# S7CAS-PLEIADES-CARTE-MERE_Pxx_IO_SENSOR.net
KiCad netlist of a schematic drawn in Altium Designer
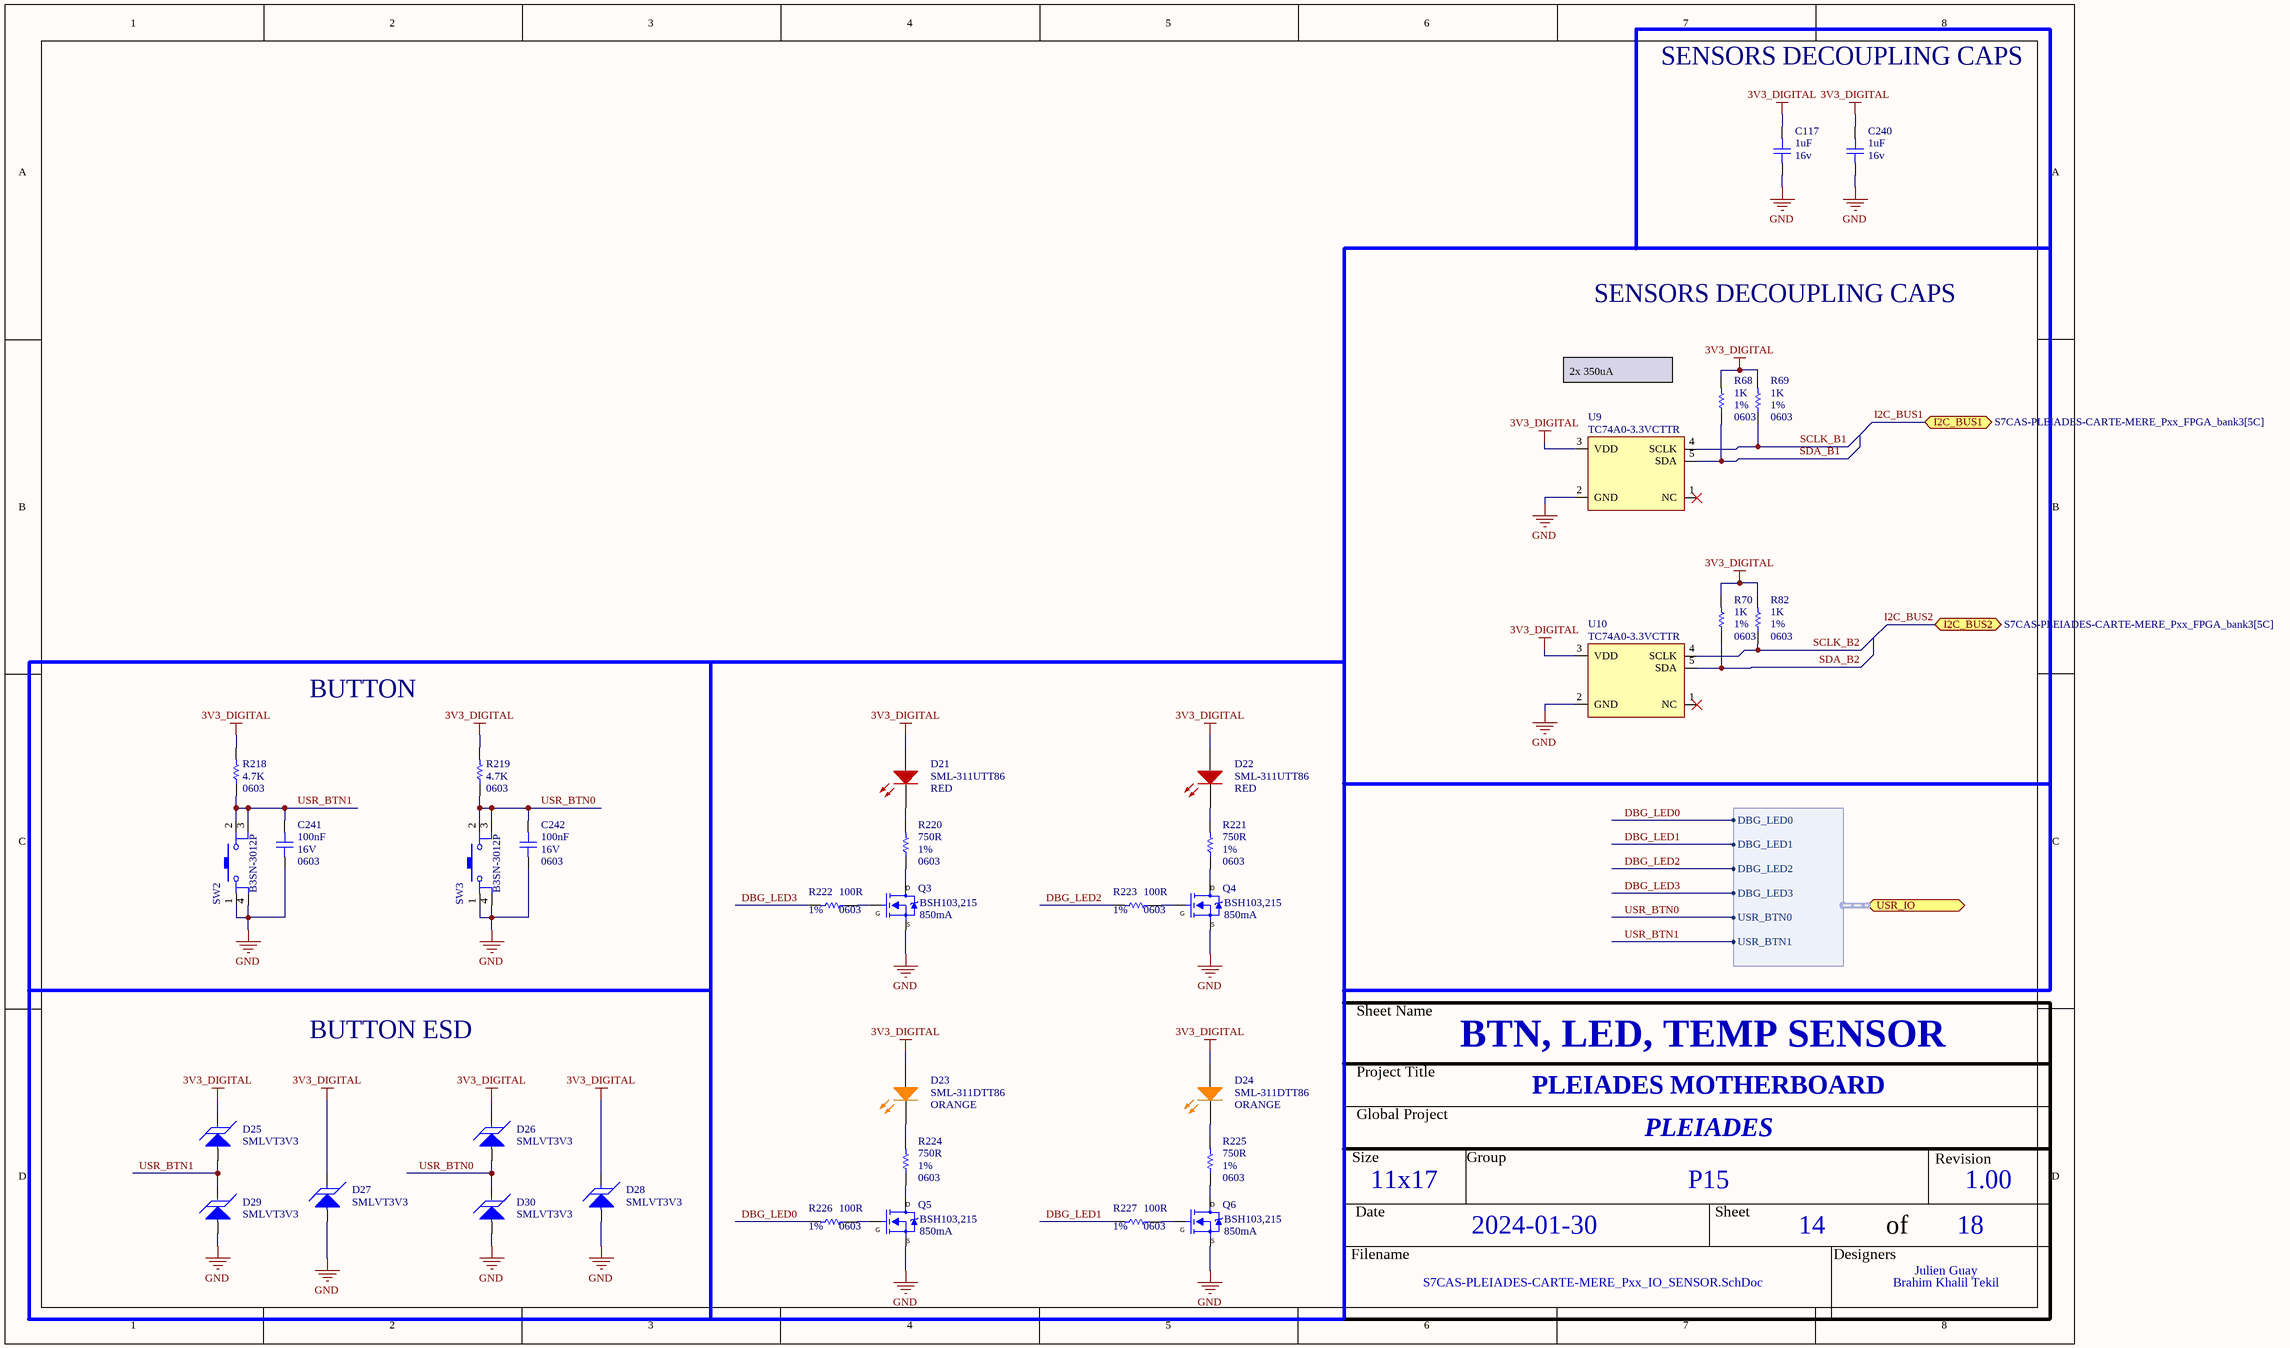
[diagram p0: S7CAS-PLEIADES-CARTE-MERE_Pxx_IO_SENSOR.SchDoc]

(export (version "E")
  (design (tool "Eeschema 10.0.6"))
  (components
    (comp (ref "C117")
      (value "1uF")
      (footprint "CAP_0603")
      (description "CAP - 0603")
      (fields (field (name "VOLTAGE") "16v") (field (name "CREATEDBY") "Jonathan Bouchard"))
      (libsource (lib "S7CAS_LIB2023") (part "CAP - 0603"))
    )
    (comp (ref "C240")
      (value "1uF")
      (footprint "CAP_0603")
      (description "CAP - 0603")
      (fields (field (name "VOLTAGE") "16v") (field (name "CREATEDBY") "Jonathan Bouchard"))
      (libsource (lib "S7CAS_LIB2023") (part "CAP - 0603"))
    )
    (comp (ref "C241")
      (value "100nF")
      (footprint "CAP_0603")
      (description "CAP - 0603")
      (fields
        (field (name "VOLTAGE") "16V")
        (field (name "PACKAGE") "0603")
        (field (name "CREATEDBY") "Jonathan Bouchard")
      )
      (libsource (lib "S7CAS_LIB2023") (part "CAP - 0603"))
    )
    (comp (ref "C242")
      (value "100nF")
      (footprint "CAP_0603")
      (description "CAP - 0603")
      (fields
        (field (name "VOLTAGE") "16V")
        (field (name "PACKAGE") "0603")
        (field (name "CREATEDBY") "Jonathan Bouchard")
      )
      (libsource (lib "S7CAS_LIB2023") (part "CAP - 0603"))
    )
    (comp (ref "D21")
      (value "SML-311UTT86")
      (footprint "LED_0603")
      (description "LED - 620nM RED 2mA - 0603")
      (fields
        (field (name "VOLTAGE") "1.8V")
        (field (name "MFG") "ROHM Semiconductor")
        (field (name "ALTIUM_VALUE") "RED")
        (field (name "CREATEDBY") "Jonathan Bouchard")
      )
      (libsource (lib "S7CAS_LIB2023") (part "LED_SML-311UTT86"))
    )
    (comp (ref "D22")
      (value "SML-311UTT86")
      (footprint "LED_0603")
      (description "LED - 620nM RED 2mA - 0603")
      (fields
        (field (name "VOLTAGE") "1.8V")
        (field (name "MFG") "ROHM Semiconductor")
        (field (name "ALTIUM_VALUE") "RED")
        (field (name "CREATEDBY") "Jonathan Bouchard")
      )
      (libsource (lib "S7CAS_LIB2023") (part "LED_SML-311UTT86"))
    )
    (comp (ref "D23")
      (value "SML-311DTT86")
      (footprint "LED_0603")
      (description "LED - 611nM ORANGE 2mA - 0603")
      (fields
        (field (name "VOLTAGE") "1.8V")
        (field (name "MFG") "ROHM Semiconductor")
        (field (name "ALTIUM_VALUE") "ORANGE")
        (field (name "CREATEDBY") "Jonathan Bouchard")
      )
      (libsource (lib "S7CAS_LIB2023") (part "LED_SML-311DTT86"))
    )
    (comp (ref "D24")
      (value "SML-311DTT86")
      (footprint "LED_0603")
      (description "LED - 611nM ORANGE 2mA - 0603")
      (fields
        (field (name "VOLTAGE") "1.8V")
        (field (name "MFG") "ROHM Semiconductor")
        (field (name "ALTIUM_VALUE") "ORANGE")
        (field (name "CREATEDBY") "Jonathan Bouchard")
      )
      (libsource (lib "S7CAS_LIB2023") (part "LED_SML-311DTT86"))
    )
    (comp (ref "D25")
      (value "SMLVT3V3")
      (footprint "TVS_POW_SMLVT3V3")
      (description "TVS - 3.3V 10.3V 600W - DO214AA")
      (fields
        (field (name "CREATEDBY/DATE") "Jonathan Bouchard - 2019-04-27")
        (field (name "VERIFIEDBY") "Nicolas V. (2019-05-06)")
      )
      (libsource (lib "S7CAS_LIB2023") (part "TVS_POW_SMLVT3V3"))
    )
    (comp (ref "D26")
      (value "SMLVT3V3")
      (footprint "TVS_POW_SMLVT3V3")
      (description "TVS - 3.3V 10.3V 600W - DO214AA")
      (fields
        (field (name "CREATEDBY/DATE") "Jonathan Bouchard - 2019-04-27")
        (field (name "VERIFIEDBY") "Nicolas V. (2019-05-06)")
      )
      (libsource (lib "S7CAS_LIB2023") (part "TVS_POW_SMLVT3V3"))
    )
    (comp (ref "D27")
      (value "SMLVT3V3")
      (footprint "TVS_POW_SMLVT3V3")
      (description "TVS - 3.3V 10.3V 600W - DO214AA")
      (fields
        (field (name "CREATEDBY/DATE") "Jonathan Bouchard - 2019-04-27")
        (field (name "VERIFIEDBY") "Nicolas V. (2019-05-06)")
      )
      (libsource (lib "S7CAS_LIB2023") (part "TVS_POW_SMLVT3V3"))
    )
    (comp (ref "D28")
      (value "SMLVT3V3")
      (footprint "TVS_POW_SMLVT3V3")
      (description "TVS - 3.3V 10.3V 600W - DO214AA")
      (fields
        (field (name "CREATEDBY/DATE") "Jonathan Bouchard - 2019-04-27")
        (field (name "VERIFIEDBY") "Nicolas V. (2019-05-06)")
      )
      (libsource (lib "S7CAS_LIB2023") (part "TVS_POW_SMLVT3V3"))
    )
    (comp (ref "D29")
      (value "SMLVT3V3")
      (footprint "TVS_POW_SMLVT3V3")
      (description "TVS - 3.3V 10.3V 600W - DO214AA")
      (fields
        (field (name "CREATEDBY/DATE") "Jonathan Bouchard - 2019-04-27")
        (field (name "VERIFIEDBY") "Nicolas V. (2019-05-06)")
      )
      (libsource (lib "S7CAS_LIB2023") (part "TVS_POW_SMLVT3V3"))
    )
    (comp (ref "D30")
      (value "SMLVT3V3")
      (footprint "TVS_POW_SMLVT3V3")
      (description "TVS - 3.3V 10.3V 600W - DO214AA")
      (fields
        (field (name "CREATEDBY/DATE") "Jonathan Bouchard - 2019-04-27")
        (field (name "VERIFIEDBY") "Nicolas V. (2019-05-06)")
      )
      (libsource (lib "S7CAS_LIB2023") (part "TVS_POW_SMLVT3V3"))
    )
    (comp (ref "Q3")
      (value "BSH103,215")
      (footprint "SOT23-3")
      (description "N-Channel  Enhancement Mode Field Effect Transistor")
      (fields (field (name "CURRENT") "850mA"))
      (libsource (lib "S7CAS_LIB2023") (part "MOS_N_CHANNEL"))
    )
    (comp (ref "Q4")
      (value "BSH103,215")
      (footprint "SOT23-3")
      (description "N-Channel  Enhancement Mode Field Effect Transistor")
      (fields (field (name "CURRENT") "850mA"))
      (libsource (lib "S7CAS_LIB2023") (part "MOS_N_CHANNEL"))
    )
    (comp (ref "Q5")
      (value "BSH103,215")
      (footprint "SOT23-3")
      (description "N-Channel  Enhancement Mode Field Effect Transistor")
      (fields (field (name "CURRENT") "850mA"))
      (libsource (lib "S7CAS_LIB2023") (part "MOS_N_CHANNEL"))
    )
    (comp (ref "Q6")
      (value "BSH103,215")
      (footprint "SOT23-3")
      (description "N-Channel  Enhancement Mode Field Effect Transistor")
      (fields (field (name "CURRENT") "850mA"))
      (libsource (lib "S7CAS_LIB2023") (part "MOS_N_CHANNEL"))
    )
    (comp (ref "R68")
      (value "1K")
      (footprint "RES_0603")
      (description "RES - 0603")
      (fields
        (field (name "PACKAGE") "0603")
        (field (name "PRECISION") "1%")
        (field (name "CREATEDBY") "Jonathan Bouchard")
      )
      (libsource (lib "S7CAS_LIB2023") (part "RES - 0603"))
    )
    (comp (ref "R69")
      (value "1K")
      (footprint "RES_0603")
      (description "RES - 0603")
      (fields
        (field (name "PACKAGE") "0603")
        (field (name "PRECISION") "1%")
        (field (name "CREATEDBY") "Jonathan Bouchard")
      )
      (libsource (lib "S7CAS_LIB2023") (part "RES - 0603"))
    )
    (comp (ref "R70")
      (value "1K")
      (footprint "RES_0603")
      (description "RES - 0603")
      (fields
        (field (name "PACKAGE") "0603")
        (field (name "PRECISION") "1%")
        (field (name "CREATEDBY") "Jonathan Bouchard")
      )
      (libsource (lib "S7CAS_LIB2023") (part "RES - 0603"))
    )
    (comp (ref "R82")
      (value "1K")
      (footprint "RES_0603")
      (description "RES - 0603")
      (fields
        (field (name "PACKAGE") "0603")
        (field (name "PRECISION") "1%")
        (field (name "CREATEDBY") "Jonathan Bouchard")
      )
      (libsource (lib "S7CAS_LIB2023") (part "RES - 0603"))
    )
    (comp (ref "R218")
      (value "4.7K")
      (footprint "RES_0603")
      (description "RES - 0603")
      (fields (field (name "PACKAGE") "0603") (field (name "CREATEDBY") "Jonathan Bouchard"))
      (libsource (lib "S7CAS_LIB2023") (part "RES - 0603"))
    )
    (comp (ref "R219")
      (value "4.7K")
      (footprint "RES_0603")
      (description "RES - 0603")
      (fields (field (name "PACKAGE") "0603") (field (name "CREATEDBY") "Jonathan Bouchard"))
      (libsource (lib "S7CAS_LIB2023") (part "RES - 0603"))
    )
    (comp (ref "R220")
      (value "750R")
      (footprint "RES_0603")
      (description "RES - 0603")
      (fields
        (field (name "PACKAGE") "0603")
        (field (name "PRECISION") "1%")
        (field (name "CREATEDBY") "Jonathan Bouchard")
      )
      (libsource (lib "S7CAS_LIB2023") (part "RES - 0603"))
    )
    (comp (ref "R221")
      (value "750R")
      (footprint "RES_0603")
      (description "RES - 0603")
      (fields
        (field (name "PACKAGE") "0603")
        (field (name "PRECISION") "1%")
        (field (name "CREATEDBY") "Jonathan Bouchard")
      )
      (libsource (lib "S7CAS_LIB2023") (part "RES - 0603"))
    )
    (comp (ref "R222")
      (value "100R")
      (footprint "RES_0603")
      (description "RES - 0603")
      (fields
        (field (name "PACKAGE") "0603")
        (field (name "PRECISION") "1%")
        (field (name "CREATEDBY") "Jonathan Bouchard")
      )
      (libsource (lib "S7CAS_LIB2023") (part "RES - 0603"))
    )
    (comp (ref "R223")
      (value "100R")
      (footprint "RES_0603")
      (description "RES - 0603")
      (fields
        (field (name "PACKAGE") "0603")
        (field (name "PRECISION") "1%")
        (field (name "CREATEDBY") "Jonathan Bouchard")
      )
      (libsource (lib "S7CAS_LIB2023") (part "RES - 0603"))
    )
    (comp (ref "R224")
      (value "750R")
      (footprint "RES_0603")
      (description "RES - 0603")
      (fields
        (field (name "PACKAGE") "0603")
        (field (name "PRECISION") "1%")
        (field (name "CREATEDBY") "Jonathan Bouchard")
      )
      (libsource (lib "S7CAS_LIB2023") (part "RES - 0603"))
    )
    (comp (ref "R225")
      (value "750R")
      (footprint "RES_0603")
      (description "RES - 0603")
      (fields
        (field (name "PACKAGE") "0603")
        (field (name "PRECISION") "1%")
        (field (name "CREATEDBY") "Jonathan Bouchard")
      )
      (libsource (lib "S7CAS_LIB2023") (part "RES - 0603"))
    )
    (comp (ref "R226")
      (value "100R")
      (footprint "RES_0603")
      (description "RES - 0603")
      (fields
        (field (name "PACKAGE") "0603")
        (field (name "PRECISION") "1%")
        (field (name "CREATEDBY") "Jonathan Bouchard")
      )
      (libsource (lib "S7CAS_LIB2023") (part "RES - 0603"))
    )
    (comp (ref "R227")
      (value "100R")
      (footprint "RES_0603")
      (description "RES - 0603")
      (fields
        (field (name "PACKAGE") "0603")
        (field (name "PRECISION") "1%")
        (field (name "CREATEDBY") "Jonathan Bouchard")
      )
      (libsource (lib "S7CAS_LIB2023") (part "RES - 0603"))
    )
    (comp (ref "SW2")
      (value "B3SN-3012P")
      (footprint "SWI_TACT_B3SN-3012P")
      (description "SWI - TACT SPST-NO 0.05A 24V - 4-SMD")
      (fields
        (field (name "MFG") "Omron")
        (field (name "VOLTAGE") "24V")
        (field (name "CREATEDBY") "Jonathan Bouchard")
      )
      (libsource (lib "S7CAS_LIB2023") (part "SWI_TACT_B3SN-3012P"))
    )
    (comp (ref "SW3")
      (value "B3SN-3012P")
      (footprint "SWI_TACT_B3SN-3012P")
      (description "SWI - TACT SPST-NO 0.05A 24V - 4-SMD")
      (fields
        (field (name "MFG") "Omron")
        (field (name "VOLTAGE") "24V")
        (field (name "CREATEDBY") "Jonathan Bouchard")
      )
      (libsource (lib "S7CAS_LIB2023") (part "SWI_TACT_B3SN-3012P"))
    )
    (comp (ref "U9")
      (value "TC74A0-3.3VCTTR")
      (footprint "SEN_TEMP_TC74A0-3.3VCTTR")
      (description "SENS - TEMPERATURE SENSOR I2C/SMBUS - SOT23-5")
      (fields
        (field (name "VOLTAGE") "2.7 V ~ 5.5 V")
        (field (name "MFG") "Microchip")
        (field (name "CREATEDBY") "Jonathan Bouchard")
      )
      (libsource (lib "S7CAS_LIB2023") (part "SENS_TEMP_TC74A0-3.3VCTTR"))
    )
    (comp (ref "U10")
      (value "TC74A0-3.3VCTTR")
      (footprint "SEN_TEMP_TC74A0-3.3VCTTR")
      (description "SENS - TEMPERATURE SENSOR I2C/SMBUS - SOT23-5")
      (fields
        (field (name "VOLTAGE") "2.7 V ~ 5.5 V")
        (field (name "MFG") "Microchip")
        (field (name "CREATEDBY") "Jonathan Bouchard")
      )
      (libsource (lib "S7CAS_LIB2023") (part "SENS_TEMP_TC74A0-3.3VCTTR"))
    )
  )
  (nets
    (net (code "4") (name "/DBG_LED0") (class "Default")
      (node (ref "R226") (pin "2") (pinfunction "2_2") (pintype "passive"))
    )
    (net (code "5") (name "/DBG_LED1") (class "Default")
      (node (ref "R227") (pin "2") (pinfunction "2_2") (pintype "passive"))
    )
    (net (code "6") (name "/DBG_LED2") (class "Default")
      (node (ref "R223") (pin "2") (pinfunction "2_2") (pintype "passive"))
    )
    (net (code "7") (name "/DBG_LED3") (class "Default")
      (node (ref "R222") (pin "2") (pinfunction "2_2") (pintype "passive"))
    )
    (net (code "8") (name "/SCLK_B1") (class "Default")
      (node (ref "R69") (pin "1") (pinfunction "1_1") (pintype "passive"))
      (node (ref "U9") (pin "4") (pinfunction "SCLK_4") (pintype "passive"))
    )
    (net (code "9") (name "/SCLK_B2") (class "Default")
      (node (ref "R82") (pin "1") (pinfunction "1_1") (pintype "passive"))
      (node (ref "U10") (pin "4") (pinfunction "SCLK_4") (pintype "passive"))
    )
    (net (code "10") (name "/SDA_B1") (class "Default")
      (node (ref "R68") (pin "1") (pinfunction "1_1") (pintype "passive"))
      (node (ref "U9") (pin "5") (pinfunction "SDA_5") (pintype "passive"))
    )
    (net (code "11") (name "/SDA_B2") (class "Default")
      (node (ref "R70") (pin "1") (pinfunction "1_1") (pintype "passive"))
      (node (ref "U10") (pin "5") (pinfunction "SDA_5") (pintype "passive"))
    )
    (net (code "12") (name "/USR_BTN0") (class "Default")
      (node (ref "C242") (pin "2") (pinfunction "2_2") (pintype "passive"))
      (node (ref "D26") (pin "A") (pinfunction "A_A") (pintype "passive"))
      (node (ref "D30") (pin "K") (pinfunction "K_K") (pintype "passive"))
      (node (ref "R219") (pin "1") (pinfunction "1_1") (pintype "passive"))
      (node (ref "SW3") (pin "2") (pinfunction "2_2") (pintype "passive"))
      (node (ref "SW3") (pin "3") (pinfunction "3_3") (pintype "passive"))
    )
    (net (code "13") (name "/USR_BTN1") (class "Default")
      (node (ref "C241") (pin "2") (pinfunction "2_2") (pintype "passive"))
      (node (ref "D25") (pin "A") (pinfunction "A_A") (pintype "passive"))
      (node (ref "D29") (pin "K") (pinfunction "K_K") (pintype "passive"))
      (node (ref "R218") (pin "1") (pinfunction "1_1") (pintype "passive"))
      (node (ref "SW2") (pin "2") (pinfunction "2_2") (pintype "passive"))
      (node (ref "SW2") (pin "3") (pinfunction "3_3") (pintype "passive"))
    )
    (net (code "17") (name "3V3_DIGITAL") (class "Default")
      (node (ref "C117") (pin "2") (pinfunction "2_2") (pintype "passive"))
      (node (ref "C240") (pin "2") (pinfunction "2_2") (pintype "passive"))
      (node (ref "D21") (pin "A") (pinfunction "A_A") (pintype "passive"))
      (node (ref "D22") (pin "A") (pinfunction "A_A") (pintype "passive"))
      (node (ref "D23") (pin "A") (pinfunction "A_A") (pintype "passive"))
      (node (ref "D24") (pin "A") (pinfunction "A_A") (pintype "passive"))
      (node (ref "D25") (pin "K") (pinfunction "K_K") (pintype "passive"))
      (node (ref "D26") (pin "K") (pinfunction "K_K") (pintype "passive"))
      (node (ref "D27") (pin "K") (pinfunction "K_K") (pintype "passive"))
      (node (ref "D28") (pin "K") (pinfunction "K_K") (pintype "passive"))
      (node (ref "R218") (pin "2") (pinfunction "2_2") (pintype "passive"))
      (node (ref "R219") (pin "2") (pinfunction "2_2") (pintype "passive"))
      (node (ref "R68") (pin "2") (pinfunction "2_2") (pintype "passive"))
      (node (ref "R69") (pin "2") (pinfunction "2_2") (pintype "passive"))
      (node (ref "R70") (pin "2") (pinfunction "2_2") (pintype "passive"))
      (node (ref "R82") (pin "2") (pinfunction "2_2") (pintype "passive"))
      (node (ref "U10") (pin "3") (pinfunction "VDD_3") (pintype "passive"))
      (node (ref "U9") (pin "3") (pinfunction "VDD_3") (pintype "passive"))
    )
    (net (code "18") (name "GND") (class "Default")
      (node (ref "C117") (pin "1") (pinfunction "1_1") (pintype "passive"))
      (node (ref "C240") (pin "1") (pinfunction "1_1") (pintype "passive"))
      (node (ref "C241") (pin "1") (pinfunction "1_1") (pintype "passive"))
      (node (ref "C242") (pin "1") (pinfunction "1_1") (pintype "passive"))
      (node (ref "D27") (pin "A") (pinfunction "A_A") (pintype "passive"))
      (node (ref "D28") (pin "A") (pinfunction "A_A") (pintype "passive"))
      (node (ref "D29") (pin "A") (pinfunction "A_A") (pintype "passive"))
      (node (ref "D30") (pin "A") (pinfunction "A_A") (pintype "passive"))
      (node (ref "Q3") (pin "2") (pintype "passive"))
      (node (ref "Q4") (pin "2") (pintype "passive"))
      (node (ref "Q5") (pin "2") (pintype "passive"))
      (node (ref "Q6") (pin "2") (pintype "passive"))
      (node (ref "SW2") (pin "1") (pinfunction "1_1") (pintype "passive"))
      (node (ref "SW2") (pin "4") (pinfunction "4_4") (pintype "passive"))
      (node (ref "SW3") (pin "1") (pinfunction "1_1") (pintype "passive"))
      (node (ref "SW3") (pin "4") (pinfunction "4_4") (pintype "passive"))
      (node (ref "U10") (pin "2") (pinfunction "GND_2") (pintype "passive"))
      (node (ref "U9") (pin "2") (pinfunction "GND_2") (pintype "passive"))
    )
    (net (code "19") (name "Net-(D21-PadK)") (class "Default")
      (node (ref "D21") (pin "K") (pinfunction "K_K") (pintype "passive"))
      (node (ref "R220") (pin "2") (pinfunction "2_2") (pintype "passive"))
    )
    (net (code "20") (name "Net-(D22-PadK)") (class "Default")
      (node (ref "D22") (pin "K") (pinfunction "K_K") (pintype "passive"))
      (node (ref "R221") (pin "2") (pinfunction "2_2") (pintype "passive"))
    )
    (net (code "21") (name "Net-(D23-PadK)") (class "Default")
      (node (ref "D23") (pin "K") (pinfunction "K_K") (pintype "passive"))
      (node (ref "R224") (pin "2") (pinfunction "2_2") (pintype "passive"))
    )
    (net (code "22") (name "Net-(D24-PadK)") (class "Default")
      (node (ref "D24") (pin "K") (pinfunction "K_K") (pintype "passive"))
      (node (ref "R225") (pin "2") (pinfunction "2_2") (pintype "passive"))
    )
    (net (code "23") (name "Net-(Q3-Pad1)") (class "Default")
      (node (ref "Q3") (pin "1") (pintype "passive"))
      (node (ref "R222") (pin "1") (pinfunction "1_1") (pintype "passive"))
    )
    (net (code "24") (name "Net-(Q3-Pad3)") (class "Default")
      (node (ref "Q3") (pin "3") (pintype "passive"))
      (node (ref "R220") (pin "1") (pinfunction "1_1") (pintype "passive"))
    )
    (net (code "25") (name "Net-(Q4-Pad1)") (class "Default")
      (node (ref "Q4") (pin "1") (pintype "passive"))
      (node (ref "R223") (pin "1") (pinfunction "1_1") (pintype "passive"))
    )
    (net (code "26") (name "Net-(Q4-Pad3)") (class "Default")
      (node (ref "Q4") (pin "3") (pintype "passive"))
      (node (ref "R221") (pin "1") (pinfunction "1_1") (pintype "passive"))
    )
    (net (code "27") (name "Net-(Q5-Pad1)") (class "Default")
      (node (ref "Q5") (pin "1") (pintype "passive"))
      (node (ref "R226") (pin "1") (pinfunction "1_1") (pintype "passive"))
    )
    (net (code "28") (name "Net-(Q5-Pad3)") (class "Default")
      (node (ref "Q5") (pin "3") (pintype "passive"))
      (node (ref "R224") (pin "1") (pinfunction "1_1") (pintype "passive"))
    )
    (net (code "29") (name "Net-(Q6-Pad1)") (class "Default")
      (node (ref "Q6") (pin "1") (pintype "passive"))
      (node (ref "R227") (pin "1") (pinfunction "1_1") (pintype "passive"))
    )
    (net (code "30") (name "Net-(Q6-Pad3)") (class "Default")
      (node (ref "Q6") (pin "3") (pintype "passive"))
      (node (ref "R225") (pin "1") (pinfunction "1_1") (pintype "passive"))
    )
    (net (code "31") (name "unconnected-(U9-NC-Pad1)") (class "Default")
      (node (ref "U9") (pin "1") (pinfunction "NC_1") (pintype "passive+no_connect"))
    )
    (net (code "32") (name "unconnected-(U10-NC-Pad1)") (class "Default")
      (node (ref "U10") (pin "1") (pinfunction "NC_1") (pintype "passive+no_connect"))
    )
  )
)
